# GC9A01.net
KiCad netlist of a schematic drawn in Altium Designer
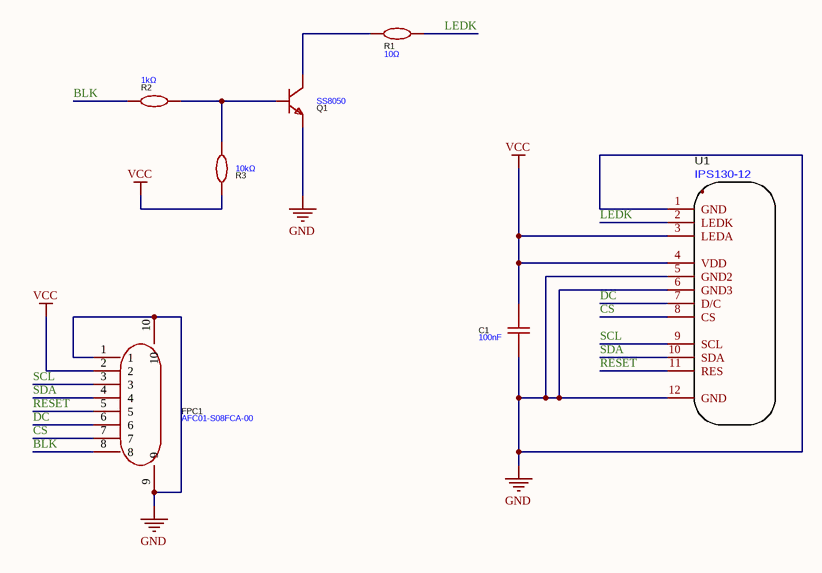
[diagram p0: GC9A01.SchDoc]

(export (version "E")
  (design (tool "Eeschema 10.0.6"))
  (components
    (comp (ref "C1")
      (value "100nF")
      (footprint "C0603")
      (fields
        (field (name "MANUFACTURER") "SAMSUNG(三星)")
        (field (name "MANUFACTURER PART") "CL10B104KB8NNNC")
        (field (name "TOLERANCE") "±10%")
      )
      (libsource (lib "電容") (part "CL10B104KB8NNNC"))
    )
    (comp (ref "FPC1")
      (value "AFC01-S08FCA-00")
      (footprint "FPC-SMD_P0.50-8P_FGS-XJ-H2.0")
      (fields (field (name "MANUFACTURER") "JS(钜硕电子)"))
      (libsource (lib "針脚") (part "AFC01-S08FCA-00"))
    )
    (comp (ref "Q1")
      (value "SS8050")
      (footprint "SOT-23-3_L2.9-W1.3-P1.90-LS2.4-BR")
      (fields (field (name "MANUFACTURER") "AnBon(安邦)"))
      (libsource (lib "三極管") (part "SS8050_C541705"))
    )
    (comp (ref "R1")
      (value "10Ω")
      (footprint "R0603")
      (fields
        (field (name "MANUFACTURER") "UNI-ROYAL(厚声)")
        (field (name "MANUFACTURER PART") "0603WAF100JT5E")
        (field (name "TOLERANCE") "±1%")
      )
      (libsource (lib "貼片電組") (part "0603WAF100JT5E"))
    )
    (comp (ref "R2")
      (value "1kΩ")
      (footprint "R0603")
      (fields
        (field (name "MANUFACTURER") "UNI-ROYAL(厚声)")
        (field (name "MANUFACTURER PART") "0603WAF1001T5E")
        (field (name "TOLERANCE") "±1%")
      )
      (libsource (lib "貼片電組") (part "0603WAF1001T5E"))
    )
    (comp (ref "R3")
      (value "10kΩ")
      (footprint "R0603")
      (fields
        (field (name "MANUFACTURER") "UNI-ROYAL(厚声)")
        (field (name "MANUFACTURER PART") "0603WAF1002T5E")
        (field (name "TOLERANCE") "±1%")
      )
      (libsource (lib "貼片電組") (part "0603WAF1002T5E"))
    )
    (comp (ref "U1")
      (value "IPS130-12")
      (footprint "FPC_0.7-12P_SMT")
      (libsource (lib "針脚") (part "IPS130-12"))
    )
  )
  (nets
    (net (code "1") (name "/BLK") (class "Default")
      (node (ref "FPC1") (pin "8") (pinfunction "8_8") (pintype "passive"))
      (node (ref "R2") (pin "1") (pinfunction "1_1") (pintype "passive"))
    )
    (net (code "2") (name "/CS") (class "Default")
      (node (ref "FPC1") (pin "7") (pinfunction "7_7") (pintype "passive"))
      (node (ref "U1") (pin "8") (pinfunction "CS_8") (pintype "passive"))
    )
    (net (code "3") (name "/DC") (class "Default")
      (node (ref "FPC1") (pin "6") (pinfunction "6_6") (pintype "passive"))
      (node (ref "U1") (pin "7") (pinfunction "D/C_7") (pintype "passive"))
    )
    (net (code "4") (name "/LEDK") (class "Default")
      (node (ref "R1") (pin "2") (pinfunction "2_2") (pintype "passive"))
      (node (ref "U1") (pin "2") (pinfunction "LEDK_2") (pintype "passive"))
    )
    (net (code "5") (name "/RESET") (class "Default")
      (node (ref "FPC1") (pin "5") (pinfunction "5_5") (pintype "passive"))
      (node (ref "U1") (pin "11") (pinfunction "RES_11") (pintype "passive"))
    )
    (net (code "6") (name "/SCL") (class "Default")
      (node (ref "FPC1") (pin "3") (pinfunction "3_3") (pintype "passive"))
      (node (ref "U1") (pin "9") (pinfunction "SCL_9") (pintype "passive"))
    )
    (net (code "7") (name "/SDA") (class "Default")
      (node (ref "FPC1") (pin "4") (pinfunction "4_4") (pintype "passive"))
      (node (ref "U1") (pin "10") (pinfunction "SDA_10") (pintype "passive"))
    )
    (net (code "8") (name "GND") (class "Default")
      (node (ref "C1") (pin "1") (pinfunction "1_1") (pintype "passive"))
      (node (ref "FPC1") (pin "1") (pinfunction "1_1") (pintype "passive"))
      (node (ref "FPC1") (pin "10") (pinfunction "10_10") (pintype "passive"))
      (node (ref "FPC1") (pin "9") (pinfunction "9_9") (pintype "passive"))
      (node (ref "Q1") (pin "2") (pinfunction "E_2") (pintype "passive"))
      (node (ref "U1") (pin "1") (pinfunction "GND_1") (pintype "passive"))
      (node (ref "U1") (pin "12") (pinfunction "GND_12") (pintype "passive"))
      (node (ref "U1") (pin "5") (pinfunction "GND2_5") (pintype "passive"))
      (node (ref "U1") (pin "6") (pinfunction "GND3_6") (pintype "passive"))
    )
    (net (code "9") (name "Net-(Q1-B)") (class "Default")
      (node (ref "Q1") (pin "1") (pinfunction "B_1") (pintype "passive"))
      (node (ref "R2") (pin "2") (pinfunction "2_2") (pintype "passive"))
      (node (ref "R3") (pin "2") (pinfunction "2_2") (pintype "passive"))
    )
    (net (code "10") (name "Net-(Q1-C)") (class "Default")
      (node (ref "Q1") (pin "3") (pinfunction "C_3") (pintype "passive"))
      (node (ref "R1") (pin "1") (pinfunction "1_1") (pintype "passive"))
    )
    (net (code "11") (name "VCC") (class "Default")
      (node (ref "C1") (pin "2") (pinfunction "2_2") (pintype "passive"))
      (node (ref "FPC1") (pin "2") (pinfunction "2_2") (pintype "passive"))
      (node (ref "R3") (pin "1") (pinfunction "1_1") (pintype "passive"))
      (node (ref "U1") (pin "3") (pinfunction "LEDA_3") (pintype "passive"))
      (node (ref "U1") (pin "4") (pinfunction "VDD_4") (pintype "passive"))
    )
  )
)
